# Sensor_Board.net
KiCad netlist of a schematic drawn in EAGLE
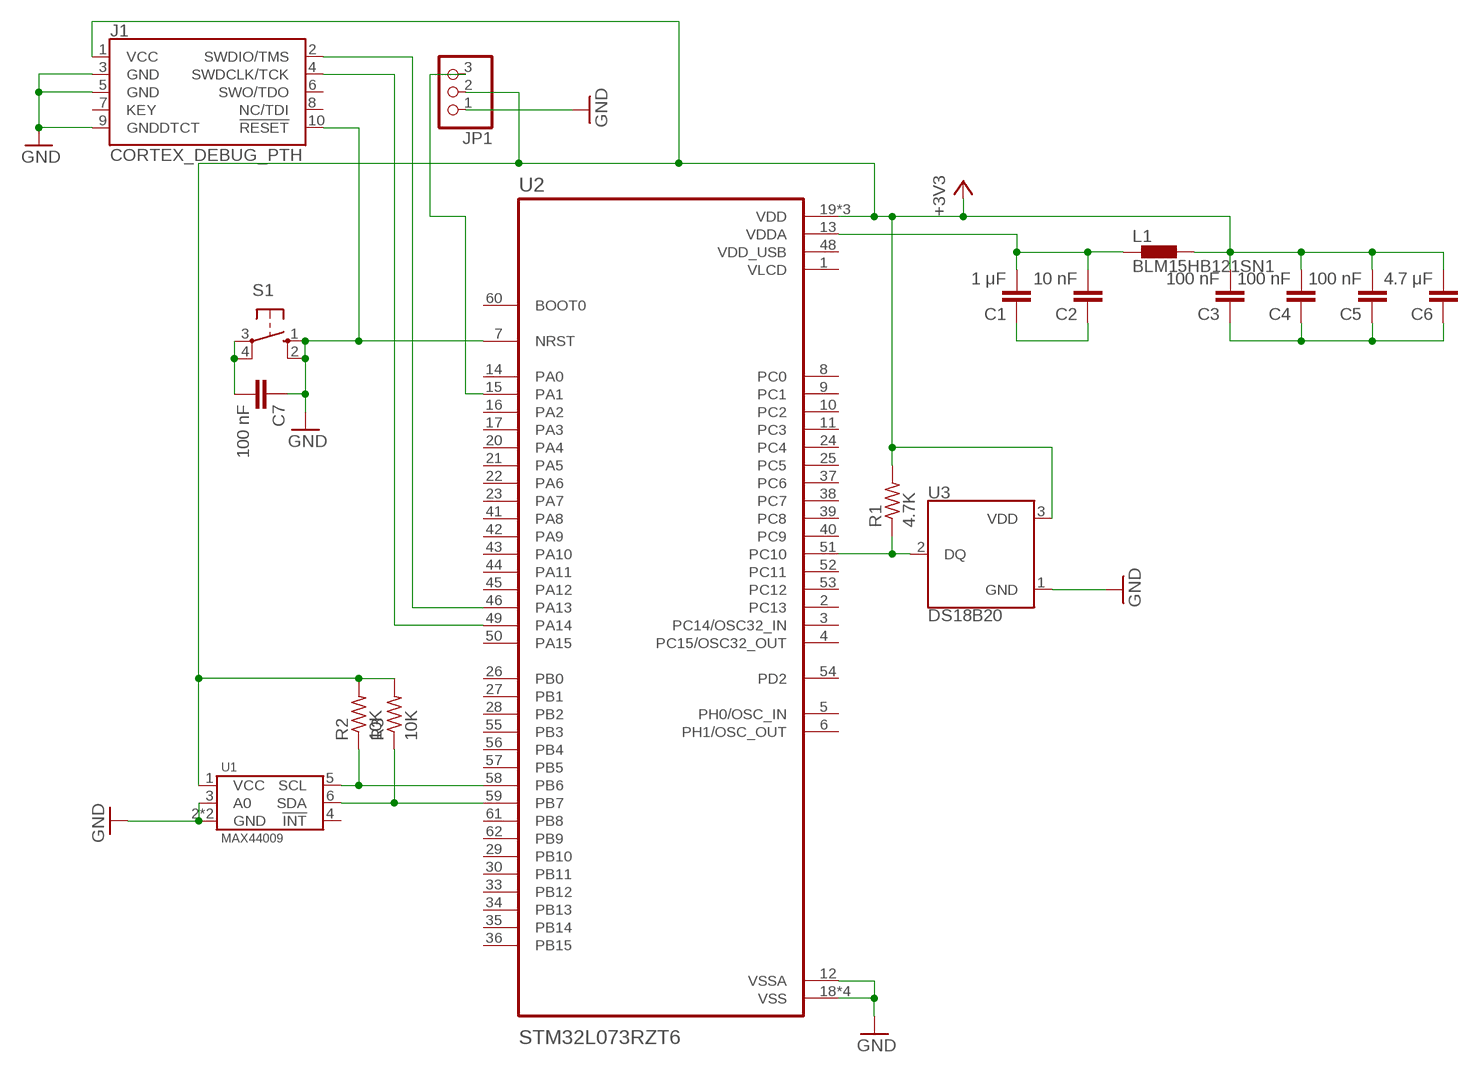
[diagram p0: schematic, sheet 1]

(export (version "E")
  (design (tool "Eeschema 10.0.6"))
  (components
    (comp (ref "C1")
      (value "1 μF")
      (footprint "eagle-import:C2.5-3")
      (libsource (lib "eagle-import") (part "C2,5-3"))
    )
    (comp (ref "C2")
      (value "10 nF")
      (footprint "eagle-import:C2.5-3")
      (libsource (lib "eagle-import") (part "C2,5-3"))
    )
    (comp (ref "C3")
      (value "100 nF")
      (footprint "eagle-import:C2.5-3")
      (libsource (lib "eagle-import") (part "C2,5-3"))
    )
    (comp (ref "C4")
      (value "100 nF")
      (footprint "eagle-import:C2.5-3")
      (libsource (lib "eagle-import") (part "C2,5-3"))
    )
    (comp (ref "C5")
      (value "100 nF")
      (footprint "eagle-import:C2.5-3")
      (libsource (lib "eagle-import") (part "C2,5-3"))
    )
    (comp (ref "C6")
      (value "4.7 μF")
      (footprint "eagle-import:C2.5-3")
      (libsource (lib "eagle-import") (part "C2,5-3"))
    )
    (comp (ref "C7")
      (value "100 nF")
      (footprint "eagle-import:C2.5-3")
      (libsource (lib "eagle-import") (part "C2,5-3"))
    )
    (comp (ref "J1")
      (value "CORTEX_DEBUG_PTH")
      (footprint "eagle-import:2X5-PTH-1.27MM")
      (libsource (lib "eagle-import") (part "CORTEX_DEBUG_PTH"))
    )
    (comp (ref "JP1")
      (value "PINHD-1X3")
      (footprint "eagle-import:1X03")
      (libsource (lib "eagle-import") (part "PINHD-1X3"))
    )
    (comp (ref "L1")
      (value "BLM15HB121SN1")
      (footprint "eagle-import:0402")
      (libsource (lib "eagle-import") (part "BLM15HB121SN1"))
    )
    (comp (ref "R1")
      (value "4.7K")
      (footprint "eagle-import:0204_5")
      (libsource (lib "eagle-import") (part "R-US_0204/5"))
    )
    (comp (ref "R2")
      (value "10K")
      (footprint "eagle-import:0204_5")
      (libsource (lib "eagle-import") (part "R-US_0204/5"))
    )
    (comp (ref "R3")
      (value "10K")
      (footprint "eagle-import:0204_5")
      (libsource (lib "eagle-import") (part "R-US_0204/5"))
    )
    (comp (ref "S1")
      (value "10-XX")
      (footprint "eagle-import:B3F-10XX")
      (fields (field (name "MPN") "B3F-1000"))
      (libsource (lib "eagle-import") (part "10-XX"))
    )
    (comp (ref "U1")
      (value "MAX44009")
      (footprint "eagle-import:MAX44009")
      (libsource (lib "eagle-import") (part "MAX44009"))
    )
    (comp (ref "U2")
      (value "STM32L073RZT6")
      (footprint "eagle-import:QFP50P1200X1200X160-64N")
      (fields (field (name "MF") "STMicroelectronics"))
      (libsource (lib "eagle-import") (part "STM32L073RZT6"))
    )
    (comp (ref "U3")
      (value "DS18B20")
      (footprint "eagle-import:TO-92-TO92127P495H2044-3")
      (fields (field (name "MF") "Maxim Integrated"))
      (libsource (lib "eagle-import") (part "DS18B20"))
    )
  )
  (nets
    (net (code "1") (name "+3V3") (class "Default")
      (node (ref "C3") (pin "2") (pinfunction "2_2") (pintype "passive"))
      (node (ref "C4") (pin "2") (pinfunction "2_2") (pintype "passive"))
      (node (ref "C5") (pin "2") (pinfunction "2_2") (pintype "passive"))
      (node (ref "C6") (pin "2") (pinfunction "2_2") (pintype "passive"))
      (node (ref "J1") (pin "1") (pinfunction "VCC_1") (pintype "bidirectional"))
      (node (ref "JP1") (pin "2") (pinfunction "2_2") (pintype "passive"))
      (node (ref "L1") (pin "2") (pinfunction "2_2") (pintype "passive"))
      (node (ref "R1") (pin "2") (pinfunction "2_2") (pintype "passive"))
      (node (ref "R2") (pin "2") (pinfunction "2_2") (pintype "passive"))
      (node (ref "R3") (pin "2") (pinfunction "2_2") (pintype "passive"))
      (node (ref "U1") (pin "1") (pinfunction "VCC_1") (pintype "bidirectional"))
      (node (ref "U2") (pin "19") (pinfunction "VDD_19") (pintype "power_in"))
      (node (ref "U2") (pin "32") (pinfunction "VDD_32") (pintype "power_in"))
      (node (ref "U2") (pin "64") (pinfunction "VDD_64") (pintype "power_in"))
      (node (ref "U3") (pin "3") (pinfunction "VDD_3") (pintype "power_in"))
    )
    (net (code "2") (name "/VDD_USB") (class "Default")
      (node (ref "U2") (pin "48") (pinfunction "VDD_USB_48") (pintype "power_in"))
    )
    (net (code "3") (name "/VLCD") (class "Default")
      (node (ref "U2") (pin "1") (pinfunction "VLCD_1") (pintype "power_in"))
    )
    (net (code "4") (name "GND") (class "Default")
      (node (ref "C7") (pin "1") (pinfunction "1_1") (pintype "passive"))
      (node (ref "J1") (pin "10") (pinfunction "~{RESET}_10") (pintype "bidirectional"))
      (node (ref "J1") (pin "3") (pinfunction "GND_3") (pintype "bidirectional"))
      (node (ref "J1") (pin "5") (pinfunction "GND_5") (pintype "bidirectional"))
      (node (ref "J1") (pin "9") (pinfunction "GNDDTCT_9") (pintype "bidirectional"))
      (node (ref "JP1") (pin "1") (pinfunction "1_1") (pintype "passive"))
      (node (ref "S1") (pin "1") (pinfunction "S_1") (pintype "passive"))
      (node (ref "S1") (pin "2") (pinfunction "S1_2") (pintype "passive"))
      (node (ref "U1") (pin "2") (pinfunction "GND_2") (pintype "bidirectional"))
      (node (ref "U1") (pin "3") (pinfunction "A0_3") (pintype "bidirectional"))
      (node (ref "U1") (pin "PAD") (pinfunction "GND_PAD") (pintype "bidirectional"))
      (node (ref "U2") (pin "12") (pinfunction "VSSA_12") (pintype "power_in"))
      (node (ref "U2") (pin "18") (pinfunction "VSS_18") (pintype "power_in"))
      (node (ref "U2") (pin "31") (pinfunction "VSS_31") (pintype "power_in"))
      (node (ref "U2") (pin "47") (pinfunction "VSS_47") (pintype "power_in"))
      (node (ref "U2") (pin "63") (pinfunction "VSS_63") (pintype "power_in"))
      (node (ref "U2") (pin "7") (pinfunction "NRST_7") (pintype "bidirectional"))
      (node (ref "U3") (pin "1") (pinfunction "GND_1") (pintype "power_in"))
    )
    (net (code "5") (name "Net-(C1-Pad1)") (class "Default")
      (node (ref "C1") (pin "1") (pinfunction "1_1") (pintype "passive"))
      (node (ref "C2") (pin "1") (pinfunction "1_1") (pintype "passive"))
    )
    (net (code "6") (name "Net-(C3-Pad1)") (class "Default")
      (node (ref "C3") (pin "1") (pinfunction "1_1") (pintype "passive"))
      (node (ref "C4") (pin "1") (pinfunction "1_1") (pintype "passive"))
      (node (ref "C5") (pin "1") (pinfunction "1_1") (pintype "passive"))
      (node (ref "C6") (pin "1") (pinfunction "1_1") (pintype "passive"))
    )
    (net (code "7") (name "Net-(J1-SWDCLK{slash}TCK)") (class "Default")
      (node (ref "J1") (pin "4") (pinfunction "SWDCLK/TCK_4") (pintype "bidirectional"))
      (node (ref "U2") (pin "49") (pinfunction "PA14_49") (pintype "bidirectional"))
    )
    (net (code "8") (name "Net-(J1-SWDIO{slash}TMS)") (class "Default")
      (node (ref "J1") (pin "2") (pinfunction "SWDIO/TMS_2") (pintype "bidirectional"))
      (node (ref "U2") (pin "46") (pinfunction "PA13_46") (pintype "bidirectional"))
    )
    (net (code "9") (name "Net-(S1-P)") (class "Default")
      (node (ref "C7") (pin "2") (pinfunction "2_2") (pintype "passive"))
      (node (ref "S1") (pin "3") (pinfunction "P_3") (pintype "passive"))
      (node (ref "S1") (pin "4") (pinfunction "P1_4") (pintype "passive"))
    )
    (net (code "10") (name "Net-(U1-SCL)") (class "Default")
      (node (ref "R2") (pin "1") (pinfunction "1_1") (pintype "passive"))
      (node (ref "U1") (pin "5") (pinfunction "SCL_5") (pintype "bidirectional"))
      (node (ref "U2") (pin "58") (pinfunction "PB6_58") (pintype "bidirectional"))
    )
    (net (code "11") (name "Net-(U1-SDA)") (class "Default")
      (node (ref "R3") (pin "1") (pinfunction "1_1") (pintype "passive"))
      (node (ref "U1") (pin "6") (pinfunction "SDA_6") (pintype "bidirectional"))
      (node (ref "U2") (pin "59") (pinfunction "PB7_59") (pintype "bidirectional"))
    )
    (net (code "12") (name "Net-(U2-PA1)") (class "Default")
      (node (ref "JP1") (pin "3") (pinfunction "3_3") (pintype "passive"))
      (node (ref "U2") (pin "15") (pinfunction "PA1_15") (pintype "bidirectional"))
    )
    (net (code "13") (name "Net-(U2-PC10)") (class "Default")
      (node (ref "R1") (pin "1") (pinfunction "1_1") (pintype "passive"))
      (node (ref "U2") (pin "51") (pinfunction "PC10_51") (pintype "bidirectional"))
      (node (ref "U3") (pin "2") (pinfunction "DQ_2") (pintype "bidirectional"))
    )
    (net (code "14") (name "Net-(U2-VDDA)") (class "Default")
      (node (ref "C1") (pin "2") (pinfunction "2_2") (pintype "passive"))
      (node (ref "C2") (pin "2") (pinfunction "2_2") (pintype "passive"))
      (node (ref "L1") (pin "1") (pinfunction "1_1") (pintype "passive"))
      (node (ref "U2") (pin "13") (pinfunction "VDDA_13") (pintype "power_in"))
    )
    (net (code "15") (name "unconnected-(J1-KEY-Pad7)") (class "Default")
      (node (ref "J1") (pin "7") (pinfunction "KEY_7") (pintype "bidirectional"))
    )
    (net (code "16") (name "unconnected-(J1-NC{slash}TDI-Pad8)") (class "Default")
      (node (ref "J1") (pin "8") (pinfunction "NC/TDI_8") (pintype "bidirectional"))
    )
    (net (code "17") (name "unconnected-(J1-SWO{slash}TDO-Pad6)") (class "Default")
      (node (ref "J1") (pin "6") (pinfunction "SWO/TDO_6") (pintype "bidirectional"))
    )
    (net (code "18") (name "unconnected-(U1-~{INT}-Pad4)") (class "Default")
      (node (ref "U1") (pin "4") (pinfunction "~{INT}_4") (pintype "bidirectional"))
    )
    (net (code "19") (name "unconnected-(U2-BOOT0-Pad60)") (class "Default")
      (node (ref "U2") (pin "60") (pinfunction "BOOT0_60") (pintype "input"))
    )
    (net (code "20") (name "unconnected-(U2-PA0-Pad14)") (class "Default")
      (node (ref "U2") (pin "14") (pinfunction "PA0_14") (pintype "bidirectional"))
    )
    (net (code "21") (name "unconnected-(U2-PA2-Pad16)") (class "Default")
      (node (ref "U2") (pin "16") (pinfunction "PA2_16") (pintype "bidirectional"))
    )
    (net (code "22") (name "unconnected-(U2-PA3-Pad17)") (class "Default")
      (node (ref "U2") (pin "17") (pinfunction "PA3_17") (pintype "bidirectional"))
    )
    (net (code "23") (name "unconnected-(U2-PA4-Pad20)") (class "Default")
      (node (ref "U2") (pin "20") (pinfunction "PA4_20") (pintype "bidirectional"))
    )
    (net (code "24") (name "unconnected-(U2-PA5-Pad21)") (class "Default")
      (node (ref "U2") (pin "21") (pinfunction "PA5_21") (pintype "bidirectional"))
    )
    (net (code "25") (name "unconnected-(U2-PA6-Pad22)") (class "Default")
      (node (ref "U2") (pin "22") (pinfunction "PA6_22") (pintype "bidirectional"))
    )
    (net (code "26") (name "unconnected-(U2-PA7-Pad23)") (class "Default")
      (node (ref "U2") (pin "23") (pinfunction "PA7_23") (pintype "bidirectional"))
    )
    (net (code "27") (name "unconnected-(U2-PA8-Pad41)") (class "Default")
      (node (ref "U2") (pin "41") (pinfunction "PA8_41") (pintype "bidirectional"))
    )
    (net (code "28") (name "unconnected-(U2-PA9-Pad42)") (class "Default")
      (node (ref "U2") (pin "42") (pinfunction "PA9_42") (pintype "bidirectional"))
    )
    (net (code "29") (name "unconnected-(U2-PA10-Pad43)") (class "Default")
      (node (ref "U2") (pin "43") (pinfunction "PA10_43") (pintype "bidirectional"))
    )
    (net (code "30") (name "unconnected-(U2-PA11-Pad44)") (class "Default")
      (node (ref "U2") (pin "44") (pinfunction "PA11_44") (pintype "bidirectional"))
    )
    (net (code "31") (name "unconnected-(U2-PA12-Pad45)") (class "Default")
      (node (ref "U2") (pin "45") (pinfunction "PA12_45") (pintype "bidirectional"))
    )
    (net (code "32") (name "unconnected-(U2-PA15-Pad50)") (class "Default")
      (node (ref "U2") (pin "50") (pinfunction "PA15_50") (pintype "bidirectional"))
    )
    (net (code "33") (name "unconnected-(U2-PB0-Pad26)") (class "Default")
      (node (ref "U2") (pin "26") (pinfunction "PB0_26") (pintype "bidirectional"))
    )
    (net (code "34") (name "unconnected-(U2-PB1-Pad27)") (class "Default")
      (node (ref "U2") (pin "27") (pinfunction "PB1_27") (pintype "bidirectional"))
    )
    (net (code "35") (name "unconnected-(U2-PB2-Pad28)") (class "Default")
      (node (ref "U2") (pin "28") (pinfunction "PB2_28") (pintype "bidirectional"))
    )
    (net (code "36") (name "unconnected-(U2-PB3-Pad55)") (class "Default")
      (node (ref "U2") (pin "55") (pinfunction "PB3_55") (pintype "bidirectional"))
    )
    (net (code "37") (name "unconnected-(U2-PB4-Pad56)") (class "Default")
      (node (ref "U2") (pin "56") (pinfunction "PB4_56") (pintype "bidirectional"))
    )
    (net (code "38") (name "unconnected-(U2-PB5-Pad57)") (class "Default")
      (node (ref "U2") (pin "57") (pinfunction "PB5_57") (pintype "bidirectional"))
    )
    (net (code "39") (name "unconnected-(U2-PB8-Pad61)") (class "Default")
      (node (ref "U2") (pin "61") (pinfunction "PB8_61") (pintype "bidirectional"))
    )
    (net (code "40") (name "unconnected-(U2-PB9-Pad62)") (class "Default")
      (node (ref "U2") (pin "62") (pinfunction "PB9_62") (pintype "bidirectional"))
    )
    (net (code "41") (name "unconnected-(U2-PB10-Pad29)") (class "Default")
      (node (ref "U2") (pin "29") (pinfunction "PB10_29") (pintype "bidirectional"))
    )
    (net (code "42") (name "unconnected-(U2-PB11-Pad30)") (class "Default")
      (node (ref "U2") (pin "30") (pinfunction "PB11_30") (pintype "bidirectional"))
    )
    (net (code "43") (name "unconnected-(U2-PB12-Pad33)") (class "Default")
      (node (ref "U2") (pin "33") (pinfunction "PB12_33") (pintype "bidirectional"))
    )
    (net (code "44") (name "unconnected-(U2-PB13-Pad34)") (class "Default")
      (node (ref "U2") (pin "34") (pinfunction "PB13_34") (pintype "bidirectional"))
    )
    (net (code "45") (name "unconnected-(U2-PB14-Pad35)") (class "Default")
      (node (ref "U2") (pin "35") (pinfunction "PB14_35") (pintype "bidirectional"))
    )
    (net (code "46") (name "unconnected-(U2-PB15-Pad36)") (class "Default")
      (node (ref "U2") (pin "36") (pinfunction "PB15_36") (pintype "bidirectional"))
    )
    (net (code "47") (name "unconnected-(U2-PC0-Pad8)") (class "Default")
      (node (ref "U2") (pin "8") (pinfunction "PC0_8") (pintype "bidirectional"))
    )
    (net (code "48") (name "unconnected-(U2-PC1-Pad9)") (class "Default")
      (node (ref "U2") (pin "9") (pinfunction "PC1_9") (pintype "bidirectional"))
    )
    (net (code "49") (name "unconnected-(U2-PC2-Pad10)") (class "Default")
      (node (ref "U2") (pin "10") (pinfunction "PC2_10") (pintype "bidirectional"))
    )
    (net (code "50") (name "unconnected-(U2-PC3-Pad11)") (class "Default")
      (node (ref "U2") (pin "11") (pinfunction "PC3_11") (pintype "bidirectional"))
    )
    (net (code "51") (name "unconnected-(U2-PC4-Pad24)") (class "Default")
      (node (ref "U2") (pin "24") (pinfunction "PC4_24") (pintype "bidirectional"))
    )
    (net (code "52") (name "unconnected-(U2-PC5-Pad25)") (class "Default")
      (node (ref "U2") (pin "25") (pinfunction "PC5_25") (pintype "bidirectional"))
    )
    (net (code "53") (name "unconnected-(U2-PC6-Pad37)") (class "Default")
      (node (ref "U2") (pin "37") (pinfunction "PC6_37") (pintype "bidirectional"))
    )
    (net (code "54") (name "unconnected-(U2-PC7-Pad38)") (class "Default")
      (node (ref "U2") (pin "38") (pinfunction "PC7_38") (pintype "bidirectional"))
    )
    (net (code "55") (name "unconnected-(U2-PC8-Pad39)") (class "Default")
      (node (ref "U2") (pin "39") (pinfunction "PC8_39") (pintype "bidirectional"))
    )
    (net (code "56") (name "unconnected-(U2-PC9-Pad40)") (class "Default")
      (node (ref "U2") (pin "40") (pinfunction "PC9_40") (pintype "bidirectional"))
    )
    (net (code "57") (name "unconnected-(U2-PC11-Pad52)") (class "Default")
      (node (ref "U2") (pin "52") (pinfunction "PC11_52") (pintype "bidirectional"))
    )
    (net (code "58") (name "unconnected-(U2-PC12-Pad53)") (class "Default")
      (node (ref "U2") (pin "53") (pinfunction "PC12_53") (pintype "bidirectional"))
    )
    (net (code "59") (name "unconnected-(U2-PC13-Pad2)") (class "Default")
      (node (ref "U2") (pin "2") (pinfunction "PC13_2") (pintype "bidirectional"))
    )
    (net (code "60") (name "unconnected-(U2-PC14{slash}OSC32_IN-Pad3)") (class "Default")
      (node (ref "U2") (pin "3") (pinfunction "PC14/OSC32_IN_3") (pintype "bidirectional"))
    )
    (net (code "61") (name "unconnected-(U2-PC15{slash}OSC32_OUT-Pad4)") (class "Default")
      (node (ref "U2") (pin "4") (pinfunction "PC15/OSC32_OUT_4") (pintype "bidirectional"))
    )
    (net (code "62") (name "unconnected-(U2-PD2-Pad54)") (class "Default")
      (node (ref "U2") (pin "54") (pinfunction "PD2_54") (pintype "bidirectional"))
    )
    (net (code "63") (name "unconnected-(U2-PH0{slash}OSC_IN-Pad5)") (class "Default")
      (node (ref "U2") (pin "5") (pinfunction "PH0/OSC_IN_5") (pintype "bidirectional"))
    )
    (net (code "64") (name "unconnected-(U2-PH1{slash}OSC_OUT-Pad6)") (class "Default")
      (node (ref "U2") (pin "6") (pinfunction "PH1/OSC_OUT_6") (pintype "bidirectional"))
    )
  )
)
